# FLASH.net
KiCad netlist of a schematic drawn in Altium Designer
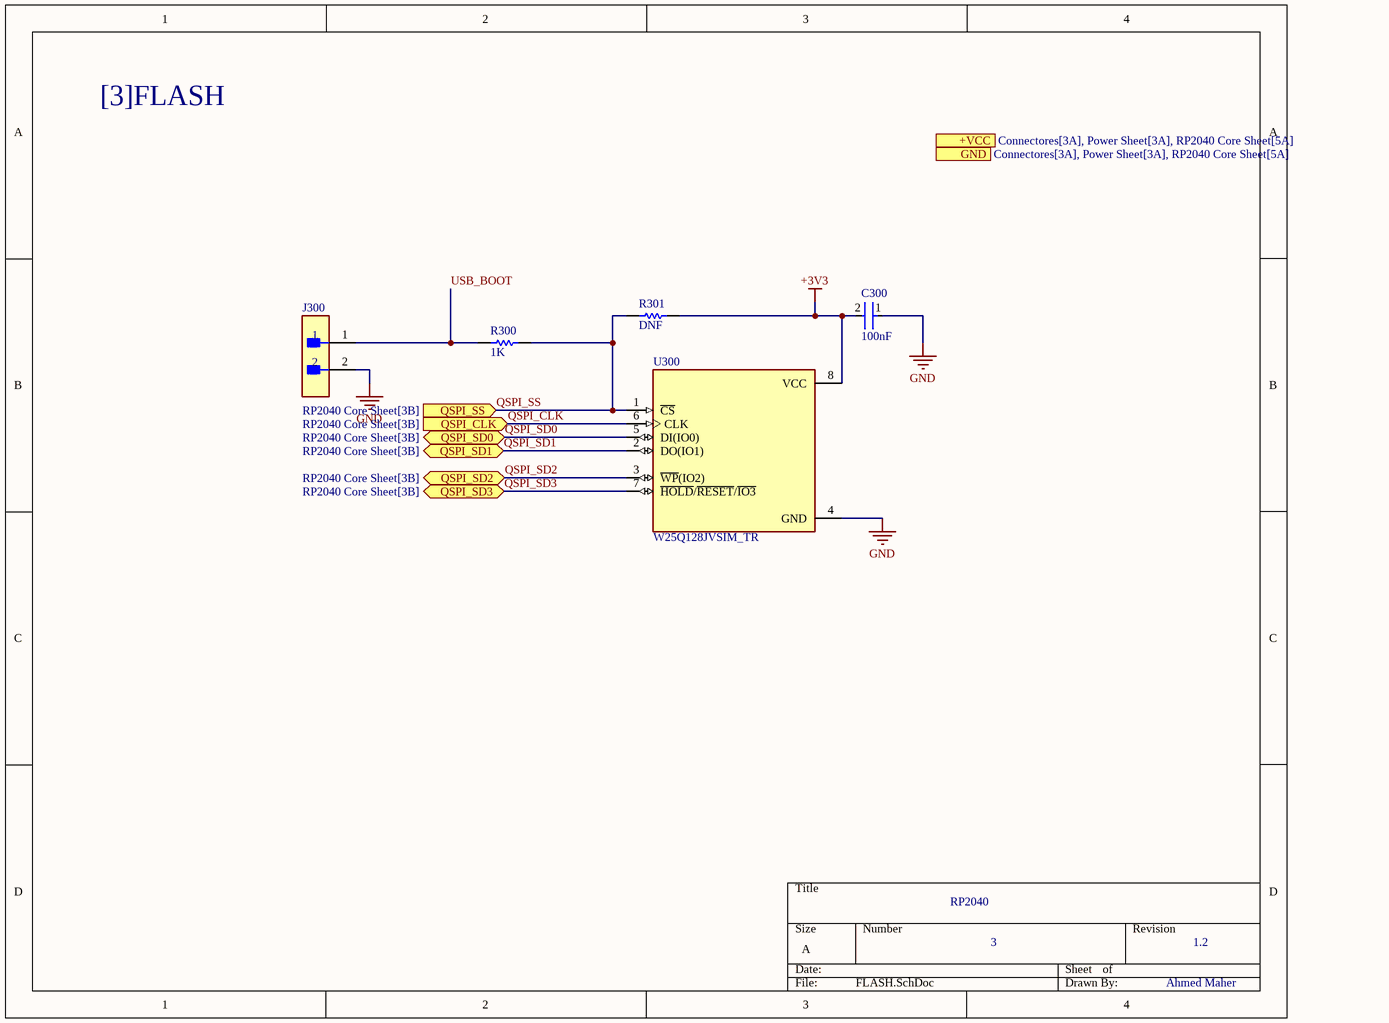
[diagram p0: FLASH.SchDoc]

(export (version "E")
  (design (tool "Eeschema 10.0.6"))
  (components
    (comp (ref "C300")
      (value "100nF")
      (footprint "FP-CGA3E-0_3-0_1-IPC_A")
      (description "Cap Ceramic 100nF 50V X7R 10% Pad SMD 0603 +125°C Automotive T/R")
      (fields (field (name "TOLERANCE") "10%") (field (name "VOLTAGE") "50V"))
      (libsource (lib "Altium Content Vault") (part "b4654b650e69147ec39a6b967a45e02"))
    )
    (comp (ref "J300")
      (value "M20-9990245")
      (footprint "FP-M20-9990245-MFG")
      (description "CONN HEADER VERT 2POS 2.54MM")
      (fields (field (name "VOLTAGE") "50V"))
      (libsource (lib "Altium Content Vault") (part "3bc925449376181038e59eaffc5286c"))
    )
    (comp (ref "R300")
      (value "1K")
      (footprint "RESC2013X60X35ML10T20")
      (description "Chip Resistor, 1 KOhm, +/- 1%, 125 mW, -55 to 155 degC, 0805 (2012 Metric), RoHS, Tape and Reel")
      (fields (field (name "TOLERANCE") "1%") (field (name "MANUFACTURER") "Yageo"))
      (libsource (lib "Altium Content Vault") (part "RES-2"))
    )
    (comp (ref "R301")
      (value "DNF")
      (footprint "RESC2013X60X35ML10T20")
      (description "Chip Resistor, 1 KOhm, +/- 1%, 125 mW, -55 to 155 degC, 0805 (2012 Metric), RoHS, Tape and Reel")
      (fields (field (name "TOLERANCE") "1%") (field (name "MANUFACTURER") "Yageo"))
      (libsource (lib "Altium Content Vault") (part "RES-2"))
    )
    (comp (ref "U300")
      (value "W25Q128JVSIM_TR")
      (footprint "SOIC127P790X216-8N")
      (description "FLASH - NOR Memory IC 128Mb (16M x 8) SPI - Quad I/O, QPI, DTR 133 MHz 8-SOIC")
      (fields (field (name "MF") "Winbond Electronics") (field (name "MP") "W25Q128JVSIM TR"))
      (libsource (lib "W25Q128JVSIM_TR") (part "W25Q128JVSIM_TR"))
    )
  )
  (nets
    (net (code "1") (name "+3V3") (class "Default")
      (node (ref "C300") (pin "2") (pinfunction "2_2") (pintype "passive"))
      (node (ref "R301") (pin "2") (pinfunction "2_2") (pintype "passive"))
      (node (ref "U300") (pin "8") (pinfunction "VCC_8") (pintype "power_in"))
    )
    (net (code "3") (name "/QSPI_CLK") (class "Default")
      (node (ref "U300") (pin "6") (pinfunction "CLK_6") (pintype "input"))
    )
    (net (code "4") (name "/QSPI_SD0") (class "Default")
      (node (ref "U300") (pin "5") (pinfunction "DI(IO0)_5") (pintype "bidirectional"))
    )
    (net (code "5") (name "/QSPI_SD1") (class "Default")
      (node (ref "U300") (pin "2") (pinfunction "DO(IO1)_2") (pintype "bidirectional"))
    )
    (net (code "6") (name "/QSPI_SD2") (class "Default")
      (node (ref "U300") (pin "3") (pinfunction "~{WP}(IO2)_3") (pintype "bidirectional"))
    )
    (net (code "7") (name "/QSPI_SD3") (class "Default")
      (node (ref "U300") (pin "7") (pinfunction "~{HOLD}/~{RESET}/~{IO3}_7") (pintype "bidirectional"))
    )
    (net (code "8") (name "/QSPI_SS") (class "Default")
      (node (ref "R300") (pin "2") (pinfunction "2_2") (pintype "passive"))
      (node (ref "R301") (pin "1") (pinfunction "1_1") (pintype "passive"))
      (node (ref "U300") (pin "1") (pinfunction "~{CS}_1") (pintype "input"))
    )
    (net (code "9") (name "/USB_BOOT") (class "Default")
      (node (ref "J300") (pin "1") (pinfunction "1_1") (pintype "passive"))
      (node (ref "R300") (pin "1") (pinfunction "1_1") (pintype "passive"))
    )
    (net (code "10") (name "GND") (class "Default")
      (node (ref "C300") (pin "1") (pinfunction "1_1") (pintype "passive"))
      (node (ref "J300") (pin "2") (pinfunction "2_2") (pintype "passive"))
      (node (ref "U300") (pin "4") (pinfunction "GND_4") (pintype "power_in"))
    )
  )
)
